# clock.net
KiCad netlist of a schematic drawn in EAGLE
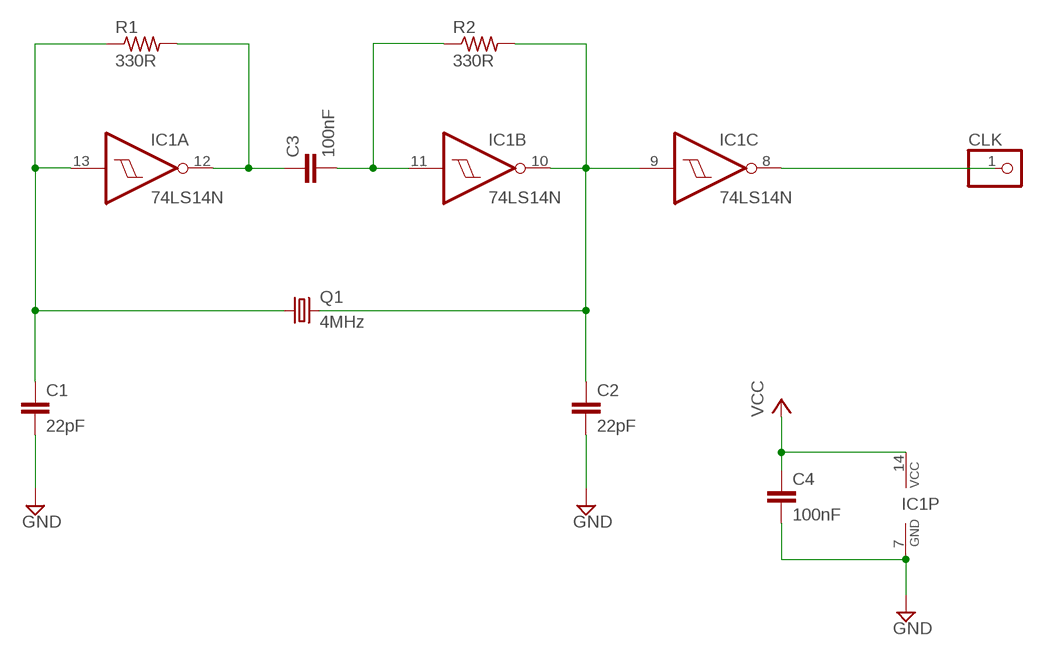
[diagram p0: schematic, sheet 1]

(export (version "E")
  (design (tool "Eeschema 10.0.6"))
  (components
    (comp (ref "C1")
      (value "22pF")
      (footprint "eagle-import:C025-025X050")
      (libsource (lib "eagle-import") (part "C-EU025-025X050"))
    )
    (comp (ref "C2")
      (value "22pF")
      (footprint "eagle-import:C025-025X050")
      (libsource (lib "eagle-import") (part "C-EU025-025X050"))
    )
    (comp (ref "C3")
      (value "100nF")
      (footprint "eagle-import:C025-025X050")
      (libsource (lib "eagle-import") (part "C-EU025-025X050"))
    )
    (comp (ref "C4")
      (value "100nF")
      (footprint "eagle-import:C025-025X050")
      (libsource (lib "eagle-import") (part "C-EU025-025X050"))
    )
    (comp (ref "CLK")
      (value "PINHD-1X1")
      (footprint "eagle-import:1X01")
      (libsource (lib "eagle-import") (part "PINHD-1X1"))
    )
    (comp (ref "IC1")
      (value "74LS14N")
      (footprint "eagle-import:DIL14")
      (libsource (lib "eagle-import") (part "7414NLS"))
    )
    (comp (ref "Q1")
      (value "4MHz")
      (footprint "eagle-import:HC49_S")
      (libsource (lib "eagle-import") (part "CRYSTALHC49S"))
    )
    (comp (ref "R1")
      (value "330R")
      (footprint "eagle-import:0207_10")
      (libsource (lib "eagle-import") (part "R-US_0207/10"))
    )
    (comp (ref "R2")
      (value "330R")
      (footprint "eagle-import:0207_10")
      (libsource (lib "eagle-import") (part "R-US_0207/10"))
    )
  )
  (nets
    (net (code "1") (name "GND") (class "Default")
      (node (ref "C1") (pin "2") (pinfunction "2_2") (pintype "passive"))
      (node (ref "C2") (pin "2") (pinfunction "2_2") (pintype "passive"))
      (node (ref "C4") (pin "2") (pinfunction "2_2") (pintype "passive"))
      (node (ref "IC1") (pin "7") (pinfunction "GND_7") (pintype "power_in"))
    )
    (net (code "2") (name "Net-(IC1A-I)") (class "Default")
      (node (ref "C1") (pin "1") (pinfunction "1_1") (pintype "passive"))
      (node (ref "IC1") (pin "13") (pinfunction "I_13") (pintype "input"))
      (node (ref "Q1") (pin "1") (pinfunction "1_1") (pintype "passive"))
      (node (ref "R1") (pin "1") (pinfunction "1_1") (pintype "passive"))
    )
    (net (code "3") (name "Net-(IC1A-O)") (class "Default")
      (node (ref "C3") (pin "1") (pinfunction "1_1") (pintype "passive"))
      (node (ref "IC1") (pin "12") (pinfunction "O_12") (pintype "output"))
      (node (ref "R1") (pin "2") (pinfunction "2_2") (pintype "passive"))
    )
    (net (code "4") (name "Net-(IC1B-I)") (class "Default")
      (node (ref "C3") (pin "2") (pinfunction "2_2") (pintype "passive"))
      (node (ref "IC1") (pin "11") (pinfunction "I_11") (pintype "input"))
      (node (ref "R2") (pin "1") (pinfunction "1_1") (pintype "passive"))
    )
    (net (code "5") (name "Net-(IC1B-O)") (class "Default")
      (node (ref "C2") (pin "1") (pinfunction "1_1") (pintype "passive"))
      (node (ref "IC1") (pin "10") (pinfunction "O_10") (pintype "output"))
      (node (ref "IC1") (pin "9") (pinfunction "I_9") (pintype "input"))
      (node (ref "Q1") (pin "2") (pinfunction "2_2") (pintype "passive"))
      (node (ref "R2") (pin "2") (pinfunction "2_2") (pintype "passive"))
    )
    (net (code "6") (name "Net-(IC1C-O)") (class "Default")
      (node (ref "CLK") (pin "1") (pinfunction "1_1") (pintype "passive"))
      (node (ref "IC1") (pin "8") (pinfunction "O_8") (pintype "output"))
    )
    (net (code "7") (name "VCC") (class "Default")
      (node (ref "C4") (pin "1") (pinfunction "1_1") (pintype "passive"))
      (node (ref "IC1") (pin "14") (pinfunction "VCC_14") (pintype "power_in"))
    )
  )
)
